# It_s_Time_Do.net
KiCad netlist of a schematic drawn in EAGLE
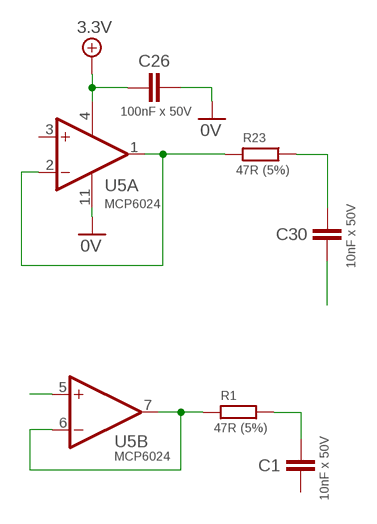
[diagram p0: schematic, sheet 1]

(export (version "E")
  (design (tool "Eeschema 10.0.6"))
  (components
    (comp (ref "C1")
      (value "10nF x 50V")
      (footprint "eagle-import:C0603")
      (libsource (lib "eagle-import") (part "C_0603"))
    )
    (comp (ref "C26")
      (value "100nF x 50V")
      (footprint "eagle-import:C0603")
      (libsource (lib "eagle-import") (part "C_0603"))
    )
    (comp (ref "C30")
      (value "10nF x 50V")
      (footprint "eagle-import:C0603")
      (libsource (lib "eagle-import") (part "C_0603"))
    )
    (comp (ref "R1")
      (value "47R (5%)")
      (footprint "eagle-import:R0603")
      (libsource (lib "eagle-import") (part "R_0603"))
    )
    (comp (ref "R23")
      (value "47R (5%)")
      (footprint "eagle-import:R0603")
      (libsource (lib "eagle-import") (part "R_0603"))
    )
    (comp (ref "U5")
      (value "MCP6024")
      (footprint "eagle-import:14-SOIC")
      (fields
        (field (name "MF") "Microchip")
        (field (name "MP") "MCP6024-I/SL")
        (field (name "PN") "MCP6024-I/SL")
      )
      (libsource (lib "eagle-import") (part "MCP6024"))
    )
  )
  (nets
    (net (code "1") (name "0V") (class "Default")
      (node (ref "C26") (pin "1") (pinfunction "1_1") (pintype "passive"))
      (node (ref "C30") (pin "2") (pinfunction "2_2") (pintype "passive"))
      (node (ref "U5") (pin "11") (pinfunction "V-_11") (pintype "power_in"))
    )
    (net (code "2") (name "3.3V") (class "Default")
      (node (ref "C26") (pin "2") (pinfunction "2_2") (pintype "passive"))
      (node (ref "U5") (pin "4") (pinfunction "V+_4") (pintype "power_in"))
    )
    (net (code "3") (name "Net-(C1-Pad1)") (class "Default")
      (node (ref "C1") (pin "1") (pinfunction "1_1") (pintype "passive"))
      (node (ref "R1") (pin "1") (pinfunction "1_1") (pintype "passive"))
    )
    (net (code "4") (name "Net-(C30-Pad1)") (class "Default")
      (node (ref "C30") (pin "1") (pinfunction "1_1") (pintype "passive"))
      (node (ref "R23") (pin "1") (pinfunction "1_1") (pintype "passive"))
    )
    (net (code "5") (name "Net-(U5A--IN)") (class "Default")
      (node (ref "R23") (pin "2") (pinfunction "2_2") (pintype "passive"))
      (node (ref "U5") (pin "1") (pinfunction "OUT_1") (pintype "output"))
      (node (ref "U5") (pin "2") (pinfunction "-IN_2") (pintype "input"))
    )
    (net (code "6") (name "Net-(U5B--IN)") (class "Default")
      (node (ref "R1") (pin "2") (pinfunction "2_2") (pintype "passive"))
      (node (ref "U5") (pin "6") (pinfunction "-IN_6") (pintype "input"))
      (node (ref "U5") (pin "7") (pinfunction "OUT_7") (pintype "output"))
    )
    (net (code "7") (name "unconnected-(C1-Pad2)") (class "Default")
      (node (ref "C1") (pin "2") (pinfunction "2_2") (pintype "passive"))
    )
    (net (code "8") (name "unconnected-(U5A-+IN-Pad3)") (class "Default")
      (node (ref "U5") (pin "3") (pinfunction "+IN_3") (pintype "input"))
    )
    (net (code "9") (name "unconnected-(U5B-+IN-Pad5)") (class "Default")
      (node (ref "U5") (pin "5") (pinfunction "+IN_5") (pintype "input"))
    )
  )
)
